# MCU_21_04_33.net
KiCad netlist of a schematic drawn in Altium Designer
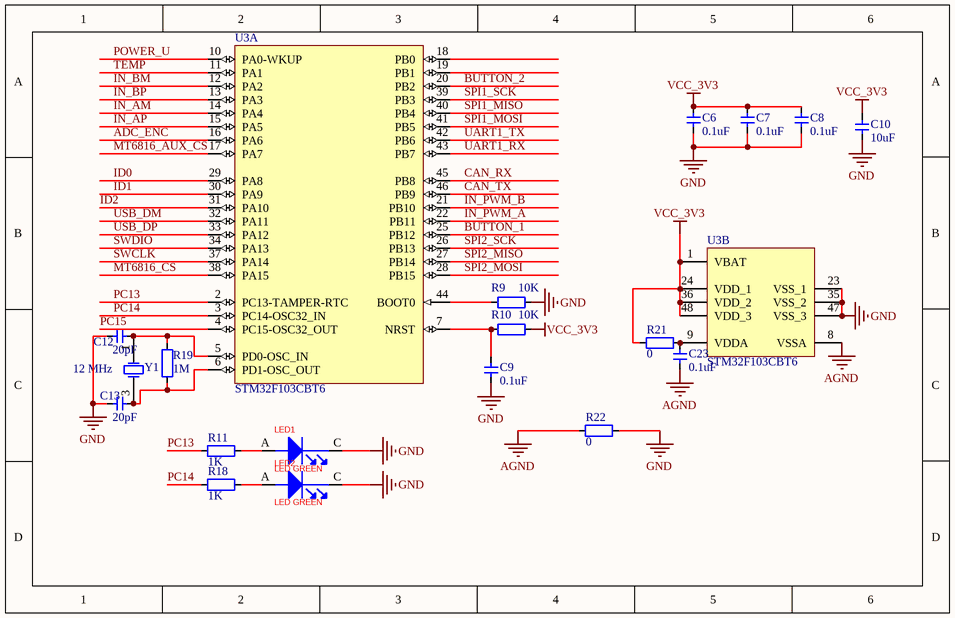
[diagram p0: MCU 21.04.33.SchDoc]

(export (version "E")
  (design (tool "Eeschema 10.0.6"))
  (components
    (comp (ref "C6")
      (value "0.1uF")
      (footprint "motor42-lib:CAP_0402")
      (description "Capacitor")
      (libsource (lib "MyPcbLib") (part "电容-0402"))
    )
    (comp (ref "C7")
      (value "0.1uF")
      (footprint "motor42-lib:CAP_0402")
      (description "Capacitor")
      (libsource (lib "MyPcbLib") (part "电容-0402"))
    )
    (comp (ref "C8")
      (value "0.1uF")
      (footprint "motor42-lib:CAP_0402")
      (description "Capacitor")
      (libsource (lib "MyPcbLib") (part "电容-0402"))
    )
    (comp (ref "C9")
      (value "0.1uF")
      (footprint "motor42-lib:CAP_0402")
      (description "Capacitor")
      (libsource (lib "MyPcbLib") (part "电容-0402"))
    )
    (comp (ref "C10")
      (value "10uF")
      (footprint "CAP_0402")
      (description "Capacitor")
      (libsource (lib "MyPcbLib") (part "电容-0402"))
    )
    (comp (ref "C12")
      (value "20pF")
      (footprint "motor42-lib:CAP_0402")
      (description "Capacitor")
      (libsource (lib "MyPcbLib") (part "电容-0402"))
    )
    (comp (ref "C13")
      (value "20pF")
      (footprint "motor42-lib:CAP_0402")
      (description "Capacitor")
      (libsource (lib "MyPcbLib") (part "电容-0402"))
    )
    (comp (ref "C23")
      (value "0.1uF")
      (footprint "motor42-lib:CAP_0402")
      (description "Capacitor")
      (libsource (lib "MyPcbLib") (part "电容-0402"))
    )
    (comp (ref "LED1")
      (value "LED GREEN")
      (footprint "LED-0603")
      (description "LED GRN SGL RA 25mA 4.1V SMD")
      (libsource (lib "*") (part "LED"))
    )
    (comp (ref "LED2")
      (value "LED GREEN")
      (footprint "LED-0603")
      (description "LED GRN SGL RA 25mA 4.1V SMD")
      (libsource (lib "*") (part "LED"))
    )
    (comp (ref "R9")
      (value "10K")
      (footprint "RES_0402")
      (description "Resistor")
      (libsource (lib "") (part "电阻-0402_1"))
    )
    (comp (ref "R10")
      (value "10K")
      (footprint "RES_0402")
      (description "Resistor")
      (libsource (lib "") (part "电阻-0402_1"))
    )
    (comp (ref "R11")
      (value "1K")
      (footprint "RES_0402")
      (description "Resistor")
      (libsource (lib "") (part "电阻-0402_1"))
    )
    (comp (ref "R18")
      (value "1K")
      (footprint "RES_0402")
      (description "Resistor")
      (libsource (lib "") (part "电阻-0402_1"))
    )
    (comp (ref "R19")
      (value "1M")
      (footprint "RES_0402")
      (description "Resistor")
      (libsource (lib "") (part "电阻-0402_2"))
    )
    (comp (ref "R21")
      (value "0")
      (footprint "RES_0402")
      (description "Resistor")
      (libsource (lib "MyPcbLib") (part "电阻-0402"))
    )
    (comp (ref "R22")
      (value "0")
      (footprint "RES_0402")
      (description "Resistor")
      (libsource (lib "MyPcbLib") (part "电阻-0402"))
    )
    (comp (ref "U3")
      (value "STM32F103CBT6")
      (footprint "motor42-lib:LQFP-48")
      (libsource (lib "STMicroelectronics STM32 F1") (part "STM32F103CBT6"))
    )
    (comp (ref "Y1")
      (value "12 MHz")
      (footprint "LC-SMD-3225_4P")
      (description "Crystal")
      (fields (field (name "Comment") "XTAL-4"))
      (libsource (lib "rpi") (part "XTAL-4"))
    )
  )
  (nets
    (net (code "1") (name "/ADC_ENC") (class "Default")
      (node (ref "U3") (pin "16") (pinfunction "PA6_16") (pintype "bidirectional"))
    )
    (net (code "2") (name "/BUTTON_1") (class "Default")
      (node (ref "U3") (pin "25") (pinfunction "PB12_25") (pintype "bidirectional"))
    )
    (net (code "3") (name "/BUTTON_2") (class "Default")
      (node (ref "U3") (pin "20") (pinfunction "PB2_20") (pintype "bidirectional"))
    )
    (net (code "4") (name "/CAN_RX") (class "Default")
      (node (ref "U3") (pin "45") (pinfunction "PB8_45") (pintype "bidirectional"))
    )
    (net (code "5") (name "/CAN_TX") (class "Default")
      (node (ref "U3") (pin "46") (pinfunction "PB9_46") (pintype "bidirectional"))
    )
    (net (code "6") (name "/ID0") (class "Default")
      (node (ref "U3") (pin "29") (pinfunction "PA8_29") (pintype "bidirectional"))
    )
    (net (code "7") (name "/ID1") (class "Default")
      (node (ref "U3") (pin "30") (pinfunction "PA9_30") (pintype "bidirectional"))
    )
    (net (code "8") (name "/ID2") (class "Default")
      (node (ref "U3") (pin "31") (pinfunction "PA10_31") (pintype "bidirectional"))
    )
    (net (code "9") (name "/IN_AM") (class "Default")
      (node (ref "U3") (pin "14") (pinfunction "PA4_14") (pintype "bidirectional"))
    )
    (net (code "10") (name "/IN_AP") (class "Default")
      (node (ref "U3") (pin "15") (pinfunction "PA5_15") (pintype "bidirectional"))
    )
    (net (code "11") (name "/IN_BM") (class "Default")
      (node (ref "U3") (pin "12") (pinfunction "PA2_12") (pintype "bidirectional"))
    )
    (net (code "12") (name "/IN_BP") (class "Default")
      (node (ref "U3") (pin "13") (pinfunction "PA3_13") (pintype "bidirectional"))
    )
    (net (code "13") (name "/IN_PWM_A") (class "Default")
      (node (ref "U3") (pin "22") (pinfunction "PB11_22") (pintype "bidirectional"))
    )
    (net (code "14") (name "/IN_PWM_B") (class "Default")
      (node (ref "U3") (pin "21") (pinfunction "PB10_21") (pintype "bidirectional"))
    )
    (net (code "15") (name "/MT6816_AUX_CS") (class "Default")
      (node (ref "U3") (pin "17") (pinfunction "PA7_17") (pintype "bidirectional"))
    )
    (net (code "16") (name "/MT6816_CS") (class "Default")
      (node (ref "U3") (pin "38") (pinfunction "PA15_38") (pintype "bidirectional"))
    )
    (net (code "17") (name "/PC13") (class "Default")
      (node (ref "R11") (pin "1") (pinfunction "1_1") (pintype "passive"))
      (node (ref "U3") (pin "2") (pinfunction "PC13-TAMPER-RTC_2") (pintype "bidirectional"))
    )
    (net (code "18") (name "/PC14") (class "Default")
      (node (ref "R18") (pin "1") (pinfunction "1_1") (pintype "passive"))
      (node (ref "U3") (pin "3") (pinfunction "PC14-OSC32_IN_3") (pintype "bidirectional"))
    )
    (net (code "19") (name "/PC15") (class "Default")
      (node (ref "U3") (pin "4") (pinfunction "PC15-OSC32_OUT_4") (pintype "bidirectional"))
    )
    (net (code "20") (name "/POWER_U") (class "Default")
      (node (ref "U3") (pin "10") (pinfunction "PA0-WKUP_10") (pintype "bidirectional"))
    )
    (net (code "21") (name "/SPI1_MISO") (class "Default")
      (node (ref "U3") (pin "40") (pinfunction "PB4_40") (pintype "bidirectional"))
    )
    (net (code "22") (name "/SPI1_MOSI") (class "Default")
      (node (ref "U3") (pin "41") (pinfunction "PB5_41") (pintype "bidirectional"))
    )
    (net (code "23") (name "/SPI1_SCK") (class "Default")
      (node (ref "U3") (pin "39") (pinfunction "PB3_39") (pintype "bidirectional"))
    )
    (net (code "24") (name "/SPI2_MISO") (class "Default")
      (node (ref "U3") (pin "27") (pinfunction "PB14_27") (pintype "bidirectional"))
    )
    (net (code "25") (name "/SPI2_MOSI") (class "Default")
      (node (ref "U3") (pin "28") (pinfunction "PB15_28") (pintype "bidirectional"))
    )
    (net (code "26") (name "/SPI2_SCK") (class "Default")
      (node (ref "U3") (pin "26") (pinfunction "PB13_26") (pintype "bidirectional"))
    )
    (net (code "27") (name "/SWCLK") (class "Default")
      (node (ref "U3") (pin "37") (pinfunction "PA14_37") (pintype "bidirectional"))
    )
    (net (code "28") (name "/SWDIO") (class "Default")
      (node (ref "U3") (pin "34") (pinfunction "PA13_34") (pintype "bidirectional"))
    )
    (net (code "29") (name "/TEMP") (class "Default")
      (node (ref "U3") (pin "11") (pinfunction "PA1_11") (pintype "bidirectional"))
    )
    (net (code "30") (name "/UART1_RX") (class "Default")
      (node (ref "U3") (pin "43") (pinfunction "PB7_43") (pintype "bidirectional"))
    )
    (net (code "31") (name "/UART1_TX") (class "Default")
      (node (ref "U3") (pin "42") (pinfunction "PB6_42") (pintype "bidirectional"))
    )
    (net (code "32") (name "/USB_DM") (class "Default")
      (node (ref "U3") (pin "32") (pinfunction "PA11_32") (pintype "bidirectional"))
    )
    (net (code "33") (name "/USB_DP") (class "Default")
      (node (ref "U3") (pin "33") (pinfunction "PA12_33") (pintype "bidirectional"))
    )
    (net (code "34") (name "AGND") (class "Default")
      (node (ref "C23") (pin "1") (pinfunction "1_1") (pintype "passive"))
      (node (ref "R22") (pin "2") (pinfunction "2_2") (pintype "passive"))
      (node (ref "U3") (pin "8") (pinfunction "VSSA_8") (pintype "power_in"))
    )
    (net (code "35") (name "GND") (class "Default")
      (node (ref "C10") (pin "1") (pinfunction "1_1") (pintype "passive"))
      (node (ref "C12") (pin "2") (pinfunction "2_2") (pintype "passive"))
      (node (ref "C13") (pin "2") (pinfunction "2_2") (pintype "passive"))
      (node (ref "C6") (pin "1") (pinfunction "1_1") (pintype "passive"))
      (node (ref "C7") (pin "1") (pinfunction "1_1") (pintype "passive"))
      (node (ref "C8") (pin "1") (pinfunction "1_1") (pintype "passive"))
      (node (ref "C9") (pin "1") (pinfunction "1_1") (pintype "passive"))
      (node (ref "LED1") (pin "C") (pinfunction "CATHODE_C") (pintype "passive"))
      (node (ref "LED2") (pin "C") (pinfunction "CATHODE_C") (pintype "passive"))
      (node (ref "R22") (pin "1") (pinfunction "1_1") (pintype "passive"))
      (node (ref "R9") (pin "2") (pinfunction "2_2") (pintype "passive"))
      (node (ref "U3") (pin "23") (pinfunction "VSS_1_23") (pintype "power_in"))
      (node (ref "U3") (pin "35") (pinfunction "VSS_2_35") (pintype "power_in"))
      (node (ref "U3") (pin "47") (pinfunction "VSS_3_47") (pintype "power_in"))
    )
    (net (code "36") (name "Net-(LED1-ANODE)") (class "Default")
      (node (ref "LED1") (pin "A") (pinfunction "ANODE_A") (pintype "passive"))
      (node (ref "R11") (pin "2") (pinfunction "2_2") (pintype "passive"))
    )
    (net (code "37") (name "Net-(LED2-ANODE)") (class "Default")
      (node (ref "LED2") (pin "A") (pinfunction "ANODE_A") (pintype "passive"))
      (node (ref "R18") (pin "2") (pinfunction "2_2") (pintype "passive"))
    )
    (net (code "38") (name "Net-(U3A-BOOT0)") (class "Default")
      (node (ref "R9") (pin "1") (pinfunction "1_1") (pintype "passive"))
      (node (ref "U3") (pin "44") (pinfunction "BOOT0_44") (pintype "input"))
    )
    (net (code "39") (name "Net-(U3A-NRST)") (class "Default")
      (node (ref "C9") (pin "2") (pinfunction "2_2") (pintype "passive"))
      (node (ref "R10") (pin "1") (pinfunction "1_1") (pintype "passive"))
      (node (ref "U3") (pin "7") (pinfunction "NRST_7") (pintype "bidirectional"))
    )
    (net (code "40") (name "Net-(U3A-PD0-OSC_IN)") (class "Default")
      (node (ref "C12") (pin "1") (pinfunction "1_1") (pintype "passive"))
      (node (ref "R19") (pin "2") (pinfunction "2_2") (pintype "passive"))
      (node (ref "U3") (pin "5") (pinfunction "PD0-OSC_IN_5") (pintype "bidirectional"))
      (node (ref "Y1") (pin "1") (pinfunction "OSC1_1") (pintype "passive"))
    )
    (net (code "41") (name "Net-(U3A-PD1-OSC_OUT)") (class "Default")
      (node (ref "C13") (pin "1") (pinfunction "1_1") (pintype "passive"))
      (node (ref "R19") (pin "1") (pinfunction "1_1") (pintype "passive"))
      (node (ref "U3") (pin "6") (pinfunction "PD1-OSC_OUT_6") (pintype "bidirectional"))
      (node (ref "Y1") (pin "3") (pinfunction "OSC2_3") (pintype "passive"))
    )
    (net (code "42") (name "Net-(U3B-VDDA)") (class "Default")
      (node (ref "C23") (pin "2") (pinfunction "2_2") (pintype "passive"))
      (node (ref "R21") (pin "1") (pinfunction "1_1") (pintype "passive"))
      (node (ref "U3") (pin "9") (pinfunction "VDDA_9") (pintype "power_in"))
    )
    (net (code "43") (name "VCC_3V3") (class "Default")
      (node (ref "C10") (pin "2") (pinfunction "2_2") (pintype "passive"))
      (node (ref "C6") (pin "2") (pinfunction "2_2") (pintype "passive"))
      (node (ref "C7") (pin "2") (pinfunction "2_2") (pintype "passive"))
      (node (ref "C8") (pin "2") (pinfunction "2_2") (pintype "passive"))
      (node (ref "R10") (pin "2") (pinfunction "2_2") (pintype "passive"))
      (node (ref "R21") (pin "2") (pinfunction "2_2") (pintype "passive"))
      (node (ref "U3") (pin "1") (pinfunction "VBAT_1") (pintype "power_in"))
      (node (ref "U3") (pin "24") (pinfunction "VDD_1_24") (pintype "power_in"))
      (node (ref "U3") (pin "36") (pinfunction "VDD_2_36") (pintype "power_in"))
      (node (ref "U3") (pin "48") (pinfunction "VDD_3_48") (pintype "power_in"))
    )
    (net (code "44") (name "unconnected-(U3A-PB0-Pad18)") (class "Default")
      (node (ref "U3") (pin "18") (pinfunction "PB0_18") (pintype "bidirectional"))
    )
    (net (code "45") (name "unconnected-(U3A-PB1-Pad19)") (class "Default")
      (node (ref "U3") (pin "19") (pinfunction "PB1_19") (pintype "bidirectional"))
    )
  )
)
